# CPU_STM32F4.net
KiCad netlist of a schematic drawn in Altium Designer
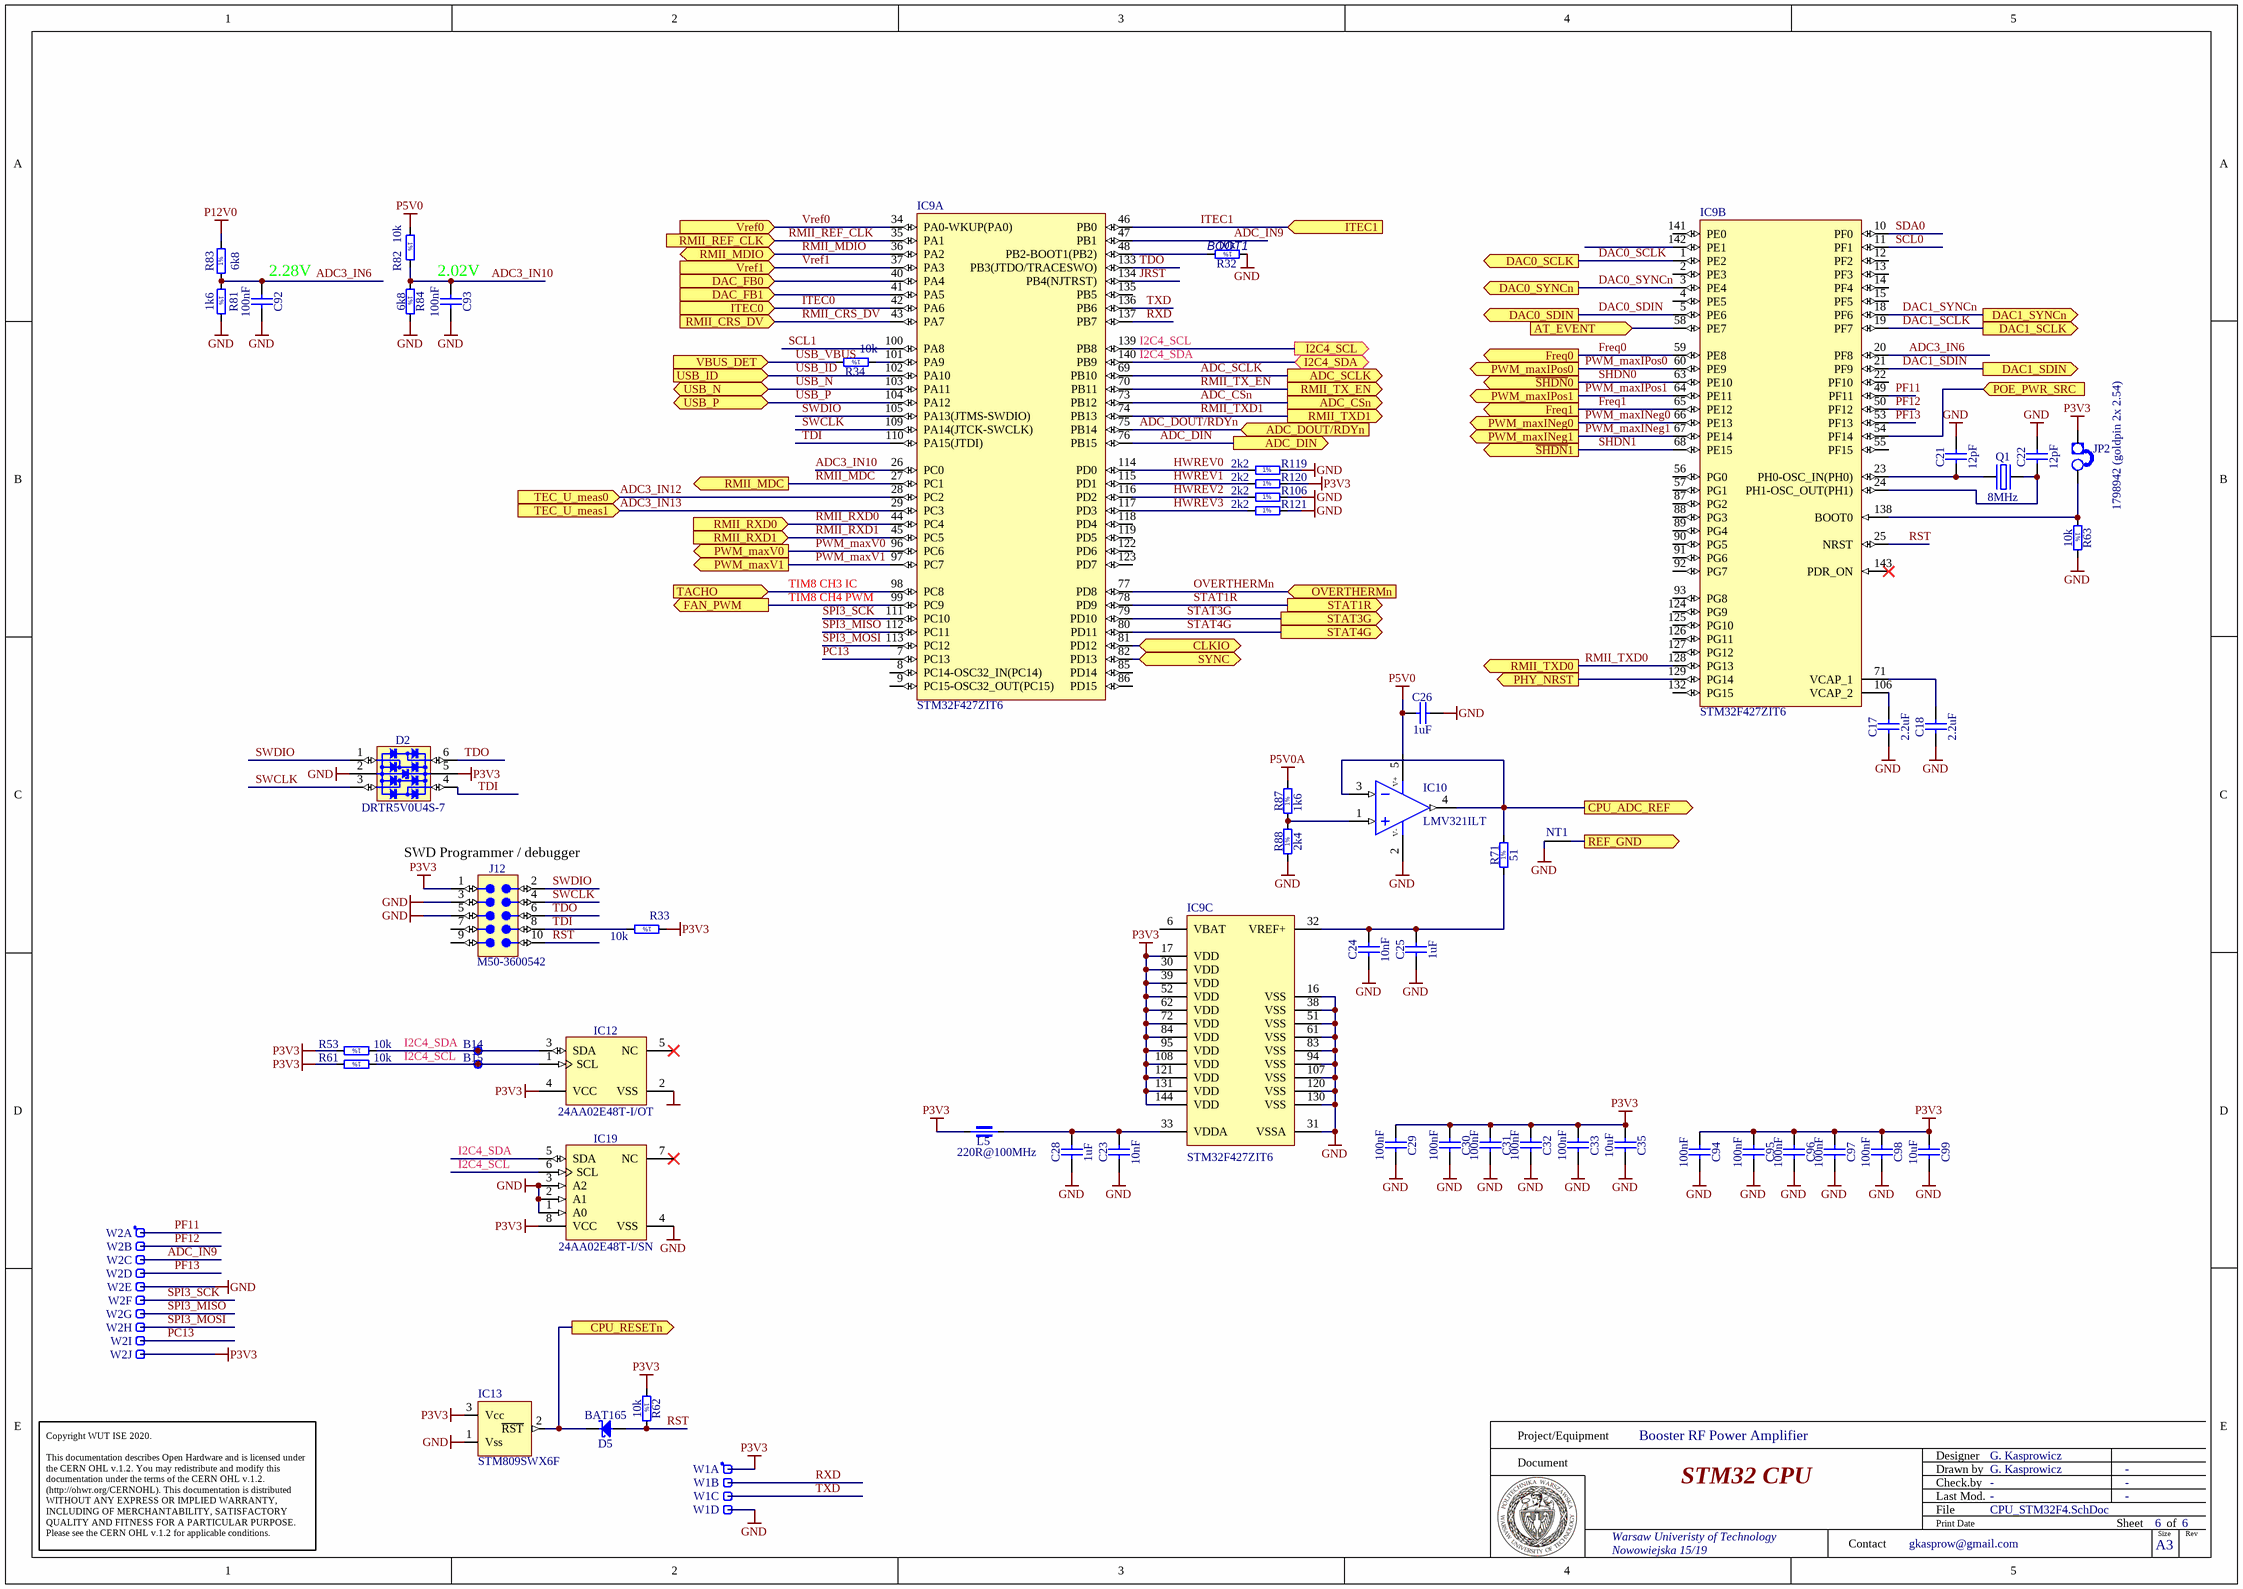
[diagram p0: CPU_STM32F4.SchDoc]

(export (version "E")
  (design (tool "Eeschema 10.0.6"))
  (components
    (comp (ref "B14")
      (value "SMD Pad")
      (footprint "C100")
      (description "Through Hole Pad")
      (fields (field (name "PART NUMBER") "SMD_PAD_D1MM") (field (name "AUTHOR") "CERN DEM JLC"))
      (libsource (lib "Eletro-mechanical") (part "Single SMD Pad (Round)"))
    )
    (comp (ref "B15")
      (value "SMD Pad")
      (footprint "C100")
      (description "Through Hole Pad")
      (fields (field (name "PART NUMBER") "SMD_PAD_D1MM") (field (name "AUTHOR") "CERN DEM JLC"))
      (libsource (lib "Eletro-mechanical") (part "Single SMD Pad (Round)"))
    )
    (comp (ref "C17")
      (value "2.2uF")
      (footprint "CAPC1608X90N")
      (description "Non-polarised capacitor")
      (fields
        (field (name "PART NUMBER") "CC0603_2.2UF_10V_20%_X7R")
        (field (name "VOLTAGE") "10V")
        (field (name "AUTHOR") "CERN DEM JLC")
      )
      (libsource (lib "Capacitors") (part "Capacitor - non polarized"))
    )
    (comp (ref "C18")
      (value "2.2uF")
      (footprint "CAPC1608X90N")
      (description "Non-polarised capacitor")
      (fields
        (field (name "PART NUMBER") "CC0603_2.2UF_10V_20%_X7R")
        (field (name "VOLTAGE") "10V")
        (field (name "AUTHOR") "CERN DEM JLC")
      )
      (libsource (lib "Capacitors") (part "Capacitor - non polarized"))
    )
    (comp (ref "C21")
      (value "12pF")
      (footprint "CAPC1005X55N")
      (description "Non-polarised capacitor")
      (fields
        (field (name "PART NUMBER") "CC0402_12PF_50V_5%_C0G")
        (field (name "VOLTAGE") "50V")
        (field (name "AUTHOR") "CERN DEM JLC")
      )
      (libsource (lib "Capacitors") (part "Capacitor - non polarized"))
    )
    (comp (ref "C22")
      (value "12pF")
      (footprint "CAPC1005X55N")
      (description "Non-polarised capacitor")
      (fields
        (field (name "PART NUMBER") "CC0402_12PF_50V_5%_C0G")
        (field (name "VOLTAGE") "50V")
        (field (name "AUTHOR") "CERN DEM JLC")
      )
      (libsource (lib "Capacitors") (part "Capacitor - non polarized"))
    )
    (comp (ref "C23")
      (value "10nF")
      (footprint "CAPC1005X55N")
      (description "Non-polarised capacitor")
      (fields
        (field (name "PART NUMBER") "CC0402_10NF_50V_10%_X7R")
        (field (name "VOLTAGE") "50V")
        (field (name "AUTHOR") "CERN DEM MR")
      )
      (libsource (lib "Capacitors") (part "Capacitor - non polarized"))
    )
    (comp (ref "C24")
      (value "10nF")
      (footprint "CAPC1005X55N")
      (description "Non-polarised capacitor")
      (fields
        (field (name "PART NUMBER") "CC0402_10NF_50V_10%_X7R")
        (field (name "VOLTAGE") "50V")
        (field (name "AUTHOR") "CERN DEM MR")
      )
      (libsource (lib "Capacitors") (part "Capacitor - non polarized"))
    )
    (comp (ref "C25")
      (value "1uF")
      (footprint "CAPC1608X87N")
      (description "Non-polarised capacitor")
      (fields
        (field (name "PART NUMBER") "CC0603_1UF_25V_10%_X7R")
        (field (name "VOLTAGE") "25V")
        (field (name "AUTHOR") "CERN DEM JLC")
      )
      (libsource (lib "Capacitors") (part "Capacitor - non polarized"))
    )
    (comp (ref "C26")
      (value "1uF")
      (footprint "CAPC1608X87N")
      (description "Non-polarised capacitor")
      (fields
        (field (name "PART NUMBER") "CC0603_1UF_25V_10%_X7R")
        (field (name "VOLTAGE") "25V")
        (field (name "AUTHOR") "CERN DEM JLC")
      )
      (libsource (lib "Capacitors") (part "Capacitor - non polarized"))
    )
    (comp (ref "C28")
      (value "1uF")
      (footprint "CAPC1608X87N")
      (description "Non-polarised capacitor")
      (fields
        (field (name "PART NUMBER") "CC0603_1UF_25V_10%_X7R")
        (field (name "VOLTAGE") "25V")
        (field (name "AUTHOR") "CERN DEM JLC")
      )
      (libsource (lib "Capacitors") (part "Capacitor - non polarized"))
    )
    (comp (ref "C29")
      (value "100nF")
      (footprint "CAPC1005X55N")
      (description "Non-polarised capacitor")
      (fields
        (field (name "PART NUMBER") "CC0402_100NF_16V_10%_X7R")
        (field (name "VOLTAGE") "16V")
        (field (name "AUTHOR") "CERN DEM JLC")
      )
      (libsource (lib "Capacitors") (part "Capacitor - non polarized"))
    )
    (comp (ref "C30")
      (value "100nF")
      (footprint "CAPC1005X55N")
      (description "Non-polarised capacitor")
      (fields
        (field (name "PART NUMBER") "CC0402_100NF_16V_10%_X7R")
        (field (name "VOLTAGE") "16V")
        (field (name "AUTHOR") "CERN DEM JLC")
      )
      (libsource (lib "Capacitors") (part "Capacitor - non polarized"))
    )
    (comp (ref "C31")
      (value "100nF")
      (footprint "CAPC1005X55N")
      (description "Non-polarised capacitor")
      (fields
        (field (name "PART NUMBER") "CC0402_100NF_16V_10%_X7R")
        (field (name "VOLTAGE") "16V")
        (field (name "AUTHOR") "CERN DEM JLC")
      )
      (libsource (lib "Capacitors") (part "Capacitor - non polarized"))
    )
    (comp (ref "C32")
      (value "100nF")
      (footprint "CAPC1005X55N")
      (description "Non-polarised capacitor")
      (fields
        (field (name "PART NUMBER") "CC0402_100NF_16V_10%_X7R")
        (field (name "VOLTAGE") "16V")
        (field (name "AUTHOR") "CERN DEM JLC")
      )
      (libsource (lib "Capacitors") (part "Capacitor - non polarized"))
    )
    (comp (ref "C33")
      (value "100nF")
      (footprint "CAPC1005X55N")
      (description "Non-polarised capacitor")
      (fields
        (field (name "PART NUMBER") "CC0402_100NF_16V_10%_X7R")
        (field (name "VOLTAGE") "16V")
        (field (name "AUTHOR") "CERN DEM JLC")
      )
      (libsource (lib "Capacitors") (part "Capacitor - non polarized"))
    )
    (comp (ref "C35")
      (value "10uF")
      (footprint "CAPC2012X135N")
      (description "Non-polarised capacitor")
      (fields
        (field (name "PART NUMBER") "CC0805_10UF_16V_10%_X5R")
        (field (name "VOLTAGE") "16V")
        (field (name "AUTHOR") "CERN DEM JLC")
      )
      (libsource (lib "Capacitors") (part "Capacitor - non polarized"))
    )
    (comp (ref "C92")
      (value "100nF")
      (footprint "CAPC1005X55N")
      (description "Non-polarised capacitor")
      (fields
        (field (name "PART NUMBER") "CC0402_100NF_16V_10%_X5R")
        (field (name "VOLTAGE") "16V")
        (field (name "AUTHOR") "CERN DEM JLC")
      )
      (libsource (lib "Capacitors") (part "Capacitor - non polarized"))
    )
    (comp (ref "C93")
      (value "100nF")
      (footprint "CAPC1005X55N")
      (description "Non-polarised capacitor")
      (fields
        (field (name "PART NUMBER") "CC0402_100NF_16V_10%_X5R")
        (field (name "VOLTAGE") "16V")
        (field (name "AUTHOR") "CERN DEM JLC")
      )
      (libsource (lib "Capacitors") (part "Capacitor - non polarized"))
    )
    (comp (ref "C94")
      (value "100nF")
      (footprint "CAPC1005X55N")
      (description "Non-polarised capacitor")
      (fields
        (field (name "PART NUMBER") "CC0402_100NF_16V_10%_X7R")
        (field (name "VOLTAGE") "16V")
        (field (name "AUTHOR") "CERN DEM JLC")
      )
      (libsource (lib "Capacitors") (part "Capacitor - non polarized"))
    )
    (comp (ref "C95")
      (value "100nF")
      (footprint "CAPC1005X55N")
      (description "Non-polarised capacitor")
      (fields
        (field (name "PART NUMBER") "CC0402_100NF_16V_10%_X7R")
        (field (name "VOLTAGE") "16V")
        (field (name "AUTHOR") "CERN DEM JLC")
      )
      (libsource (lib "Capacitors") (part "Capacitor - non polarized"))
    )
    (comp (ref "C96")
      (value "100nF")
      (footprint "CAPC1005X55N")
      (description "Non-polarised capacitor")
      (fields
        (field (name "PART NUMBER") "CC0402_100NF_16V_10%_X7R")
        (field (name "VOLTAGE") "16V")
        (field (name "AUTHOR") "CERN DEM JLC")
      )
      (libsource (lib "Capacitors") (part "Capacitor - non polarized"))
    )
    (comp (ref "C97")
      (value "100nF")
      (footprint "CAPC1005X55N")
      (description "Non-polarised capacitor")
      (fields
        (field (name "PART NUMBER") "CC0402_100NF_16V_10%_X7R")
        (field (name "VOLTAGE") "16V")
        (field (name "AUTHOR") "CERN DEM JLC")
      )
      (libsource (lib "Capacitors") (part "Capacitor - non polarized"))
    )
    (comp (ref "C98")
      (value "100nF")
      (footprint "CAPC1005X55N")
      (description "Non-polarised capacitor")
      (fields
        (field (name "PART NUMBER") "CC0402_100NF_16V_10%_X7R")
        (field (name "VOLTAGE") "16V")
        (field (name "AUTHOR") "CERN DEM JLC")
      )
      (libsource (lib "Capacitors") (part "Capacitor - non polarized"))
    )
    (comp (ref "C99")
      (value "10uF")
      (footprint "CAPC2012X135N")
      (description "Non-polarised capacitor")
      (fields
        (field (name "PART NUMBER") "CC0805_10UF_16V_10%_X5R")
        (field (name "VOLTAGE") "16V")
        (field (name "AUTHOR") "CERN DEM JLC")
      )
      (libsource (lib "Capacitors") (part "Capacitor - non polarized"))
    )
    (comp (ref "D2")
      (value "DRTR5V0U4S-7")
      (footprint "SOT65P210X110-6N")
      (description "Integrated Quad Ultra-Low Capacitance ESD Protection")
      (fields (field (name "MANUFACTURER") "DIODES") (field (name "AUTHOR") "GK"))
      (libsource (lib "Diodes") (part "D_TVS_DRTR5V0U4S-7"))
    )
    (comp (ref "D5")
      (value "BAT165")
      (footprint "SOD2512X110N")
      (description "Schottky Diode")
      (fields
        (field (name "VOLTAGE") "40V")
        (field (name "POWER") "750mA")
        (field (name "AUTHOR") "CERN DEM JLC")
      )
      (libsource (lib "ICs And Semiconductors") (part "Diode Schottky"))
    )
    (comp (ref "IC9")
      (value "STM32F427ZIT6")
      (footprint "STM-LQFP144_V")
      (fields (field (name "MANUFACTURER") "STMicroelectronics"))
      (libsource (lib "Altium Content Vault") (part "MC-ARM-STM32F427-SQ144"))
    )
    (comp (ref "IC10")
      (value "LMV321ILT")
      (footprint "SOT95P280X145-5N")
      (description "Operational Amplifier")
      (fields (field (name "MANUFACTURER") "ST MICROELECTRONICS") (field (name "AUTHOR") "CERN DEM MR"))
      (libsource (lib "ICs And Semiconductors") (part "Operational Amplifier Type10"))
    )
    (comp (ref "IC12")
      (value "24AA02E48T-I/OT")
      (footprint "SOT95P280X145-5N")
      (description "1.7V-5.5V, 2K I2C Serial EEPROM With EUI-48 Node Identity")
      (fields (field (name "MANUFACTURER") "MICROCHIP TECHNOLOGY") (field (name "AUTHOR") "CERN DEM MR"))
      (libsource (lib "ICs And Semiconductors") (part "24AA02E48T-I/OT"))
    )
    (comp (ref "IC13")
      (value "STM809SWX6F")
      (footprint "SOT-23")
      (description "2.93V  Reset circuit")
      (libsource (lib "LIBRARY_SCH") (part "VMON_STM809"))
    )
    (comp (ref "IC19")
      (value "24AA02E48T-I/SN")
      (footprint "SOIC127P600X175-8N")
      (description "1.7V-5.5V, 2K I2C™ Serial EEPROMs with EUI-48™ Node Identity")
      (fields (field (name "MANUFACTURER") "MICROCHIP TECHNOLOGY") (field (name "AUTHOR") "GK"))
      (libsource (lib "ICS-logic") (part "MEM_24AA02E48T-I/SN"))
    )
    (comp (ref "J12")
      (value "Header 10")
      (footprint "HARWIN_M50-3600542")
      (description "10 Contacts - Pitch 1.27mm - Dual Row SMT Vertical Pin Header (Post Lead = 3mm, Insulator 1mm)")
      (fields
        (field (name "PART NUMBER") "HARWIN_M50-3600542")
        (field (name "MANUFACTURER") "HARWIN")
        (field (name "MANUFACTURER PART NUMBER") "M50-3600542")
        (field (name "AUTHOR") "GK")
      )
      (libsource (lib "Connectors") (part "CON_2x10 1.27 SMT_male_HARWIN"))
    )
    (comp (ref "JP2")
      (value "1798942 (goldpin 2x 2.54)")
      (footprint "jump")
      (description "Jumper")
      (libsource (lib "LIBRARY_SCH") (part "JUMPER"))
    )
    (comp (ref "L5")
      (value "220R@100MHz")
      (footprint "INDC1005X55N")
      (fields
        (field (name "PART NUMBER") "IND0402_MURATA_BLM15HB221SN1")
        (field (name "POWER") "250mA")
        (field (name "TOLERANCE") "±25%")
        (field (name "AUTHOR") "CERN DEM JLC")
      )
      (libsource (lib "Inductors & Transformers") (part "Ferrite Bead"))
    )
    (comp (ref "NT1")
      (value "Net Tie")
      (footprint "Net Tie")
      (fields (field (name "AUTHOR") "CERN DEM JLC"))
      (libsource (lib "Eletro-mechanical") (part "Net Tie"))
    )
    (comp (ref "Q1")
      (value "8MHz")
      (footprint "XTAL_TXC_7A")
      (description "Quartz Crystal")
      (fields
        (field (name "PART NUMBER") "XTAL_8MHZ_TXC_7A-8.000MAAE-T")
        (field (name "MANUFACTURER") "TXC CORPORATION")
        (field (name "AUTHOR") "CERN DEM JLC")
      )
      (libsource (lib "ICs And Semiconductors") (part "Quartz Crystal"))
    )
    (comp (ref "R32")
      (value "10k")
      (footprint "RESC1005X40N")
      (description "Resistor - 1%")
      (fields
        (field (name "PART NUMBER") "R0402_10K_1%_0.0625W_100PPM")
        (field (name "POWER") "0.0625W")
        (field (name "AUTHOR") "CERN DEM JLC")
      )
      (libsource (lib "Resistors") (part "Resistor - 1%"))
    )
    (comp (ref "R33")
      (value "10k")
      (footprint "RESC1005X40N")
      (description "Resistor - 1%")
      (fields
        (field (name "PART NUMBER") "R0402_10K_1%_0.0625W_100PPM")
        (field (name "POWER") "0.0625W")
        (field (name "AUTHOR") "CERN DEM JLC")
      )
      (libsource (lib "Resistors") (part "Resistor - 1%"))
    )
    (comp (ref "R34")
      (value "10k")
      (footprint "RESC1005X40N")
      (description "Resistor - 1%")
      (fields
        (field (name "PART NUMBER") "R0402_10K_1%_0.0625W_100PPM")
        (field (name "POWER") "0.0625W")
        (field (name "AUTHOR") "CERN DEM JLC")
      )
      (libsource (lib "Resistors") (part "Resistor - 1%"))
    )
    (comp (ref "R53")
      (value "10k")
      (footprint "RESC1005X40N")
      (description "Resistor - 1%")
      (fields
        (field (name "PART NUMBER") "R0402_10K_1%_0.0625W_100PPM")
        (field (name "POWER") "0.0625W")
        (field (name "AUTHOR") "CERN DEM JLC")
      )
      (libsource (lib "Resistors") (part "Resistor - 1%"))
    )
    (comp (ref "R61")
      (value "10k")
      (footprint "RESC1005X40N")
      (description "Resistor - 1%")
      (fields
        (field (name "PART NUMBER") "R0402_10K_1%_0.0625W_100PPM")
        (field (name "POWER") "0.0625W")
        (field (name "AUTHOR") "CERN DEM JLC")
      )
      (libsource (lib "Resistors") (part "Resistor - 1%"))
    )
    (comp (ref "R62")
      (value "10k")
      (footprint "RESC1005X40N")
      (description "Resistor - 1%")
      (fields
        (field (name "PART NUMBER") "R0402_10K_1%_0.0625W_100PPM")
        (field (name "POWER") "0.0625W")
        (field (name "AUTHOR") "CERN DEM JLC")
      )
      (libsource (lib "Resistors") (part "Resistor - 1%"))
    )
    (comp (ref "R63")
      (value "10k")
      (footprint "RESC1005X40N")
      (description "Resistor - 1%")
      (fields
        (field (name "PART NUMBER") "R0402_10K_1%_0.0625W_100PPM")
        (field (name "POWER") "0.0625W")
        (field (name "AUTHOR") "CERN DEM JLC")
      )
      (libsource (lib "Resistors") (part "Resistor - 1%"))
    )
    (comp (ref "R71")
      (value "51")
      (footprint "RESC1005X40N")
      (description "Resistor - 1%")
      (fields
        (field (name "PART NUMBER") "R0402_51R_1%_0.0625W_100PPM")
        (field (name "POWER") "0.0625W")
        (field (name "AUTHOR") "CERN DEM JLC")
      )
      (libsource (lib "Resistors") (part "Resistor - 1%"))
    )
    (comp (ref "R81")
      (value "1k6")
      (footprint "RESC1005X40N")
      (description "Resistor - 1%")
      (fields
        (field (name "PART NUMBER") "R0402_1K6_1%_0.0625W_100PPM")
        (field (name "POWER") "0.0625W")
        (field (name "AUTHOR") "CERN DEM JLC")
      )
      (libsource (lib "Resistors") (part "Resistor - 1%"))
    )
    (comp (ref "R82")
      (value "10k")
      (footprint "RESC1005X40N")
      (description "Resistor - 1%")
      (fields
        (field (name "PART NUMBER") "R0402_10K_1%_0.0625W_100PPM")
        (field (name "POWER") "0.0625W")
        (field (name "AUTHOR") "CERN DEM JLC")
      )
      (libsource (lib "Resistors") (part "Resistor - 1%"))
    )
    (comp (ref "R83")
      (value "6k8")
      (footprint "RESC1005X40N")
      (description "Resistor - 1%")
      (fields
        (field (name "PART NUMBER") "R0402_6K8_1%_0.0625W_100PPM")
        (field (name "POWER") "0.0625W")
        (field (name "AUTHOR") "CERN DEM JLC")
      )
      (libsource (lib "Resistors") (part "Resistor - 1%"))
    )
    (comp (ref "R84")
      (value "6k8")
      (footprint "RESC1005X40N")
      (description "Resistor - 1%")
      (fields
        (field (name "PART NUMBER") "R0402_6K8_1%_0.0625W_100PPM")
        (field (name "POWER") "0.0625W")
        (field (name "AUTHOR") "CERN DEM JLC")
      )
      (libsource (lib "Resistors") (part "Resistor - 1%"))
    )
    (comp (ref "R87")
      (value "1k6")
      (footprint "RESC1005X40N")
      (description "Resistor - 1%")
      (fields
        (field (name "PART NUMBER") "R0402_1K6_1%_0.0625W_100PPM")
        (field (name "POWER") "0.0625W")
        (field (name "AUTHOR") "CERN DEM JLC")
      )
      (libsource (lib "Resistors") (part "Resistor - 1%"))
    )
    (comp (ref "R88")
      (value "2k4")
      (footprint "RESC1005X40N")
      (description "Resistor - 1%")
      (fields
        (field (name "PART NUMBER") "R0402_2K4_1%_0.0625W_100PPM")
        (field (name "POWER") "0.0625W")
        (field (name "AUTHOR") "CERN DEM JLC")
      )
      (libsource (lib "Resistors") (part "Resistor - 1%"))
    )
    (comp (ref "R106")
      (value "2k2")
      (footprint "RESC1005X40N")
      (description "Resistor - 1%")
      (fields
        (field (name "PART NUMBER") "R0402_2K2_1%_0.0625W_100PPM")
        (field (name "POWER") "0.0625W")
        (field (name "AUTHOR") "CERN DEM JLC")
      )
      (libsource (lib "Resistors") (part "Resistor - 1%"))
    )
    (comp (ref "R119")
      (value "2k2")
      (footprint "RESC1005X40N")
      (description "Resistor - 1%")
      (fields
        (field (name "PART NUMBER") "R0402_2K2_1%_0.0625W_100PPM")
        (field (name "POWER") "0.0625W")
        (field (name "AUTHOR") "CERN DEM JLC")
      )
      (libsource (lib "Resistors") (part "Resistor - 1%"))
    )
    (comp (ref "R120")
      (value "2k2")
      (footprint "RESC1005X40N")
      (description "Resistor - 1%")
      (fields
        (field (name "PART NUMBER") "R0402_2K2_1%_0.0625W_100PPM")
        (field (name "POWER") "0.0625W")
        (field (name "AUTHOR") "CERN DEM JLC")
      )
      (libsource (lib "Resistors") (part "Resistor - 1%"))
    )
    (comp (ref "R121")
      (value "2k2")
      (footprint "RESC1005X40N")
      (description "Resistor - 1%")
      (fields
        (field (name "PART NUMBER") "R0402_2K2_1%_0.0625W_100PPM")
        (field (name "POWER") "0.0625W")
        (field (name "AUTHOR") "CERN DEM JLC")
      )
      (libsource (lib "Resistors") (part "Resistor - 1%"))
    )
    (comp (ref "W1")
      (value "Header 4")
      (footprint "SAMTEC_HTSW-104-23-L-S")
      (description "4 Mini Wire-Wrap Contact Strip Header")
      (fields
        (field (name "PART NUMBER") "SAMTEC_HTSW-104-23-L-S")
        (field (name "MANUFACTURER") "SAMTEC")
        (field (name "AUTHOR") "CERN DEM JLC")
      )
      (libsource (lib "Connectors") (part "Wire-Wrap Contact x4"))
    )
    (comp (ref "W2")
      (value "Header 10")
      (footprint "SAMTEC_MTLW-110-07-L-S-250")
      (description "10 Mini Wire-Wrap Contact Strip Header")
      (fields
        (field (name "PART NUMBER") "SAMTEC_MTLW-110-07-L-S-250")
        (field (name "MANUFACTURER") "SAMTEC")
        (field (name "AUTHOR") "CERN DEM JLC")
      )
      (libsource (lib "Connectors") (part "Wire-Wrap Contact x10"))
    )
  )
  (nets
    (net (code "1") (name "/ADC3_IN6") (class "Default")
      (node (ref "C92") (pin "1") (pinfunction "1_1") (pintype "passive"))
      (node (ref "IC9") (pin "20") (pinfunction "PF8_20") (pintype "bidirectional"))
      (node (ref "R81") (pin "1") (pinfunction "1_1") (pintype "passive"))
      (node (ref "R83") (pin "1") (pinfunction "1_1") (pintype "passive"))
    )
    (net (code "2") (name "/ADC3_IN10") (class "Default")
      (node (ref "C93") (pin "1") (pinfunction "1_1") (pintype "passive"))
      (node (ref "IC9") (pin "26") (pinfunction "PC0_26") (pintype "bidirectional"))
      (node (ref "R82") (pin "2") (pinfunction "2_2") (pintype "passive"))
      (node (ref "R84") (pin "1") (pinfunction "1_1") (pintype "passive"))
    )
    (net (code "3") (name "/ADC3_IN12") (class "Default")
      (node (ref "IC9") (pin "28") (pinfunction "PC2_28") (pintype "bidirectional"))
    )
    (net (code "4") (name "/ADC3_IN13") (class "Default")
      (node (ref "IC9") (pin "29") (pinfunction "PC3_29") (pintype "bidirectional"))
    )
    (net (code "5") (name "/ADC_CSn") (class "Default")
      (node (ref "IC9") (pin "73") (pinfunction "PB12_73") (pintype "bidirectional"))
    )
    (net (code "6") (name "/ADC_DIN") (class "Default")
      (node (ref "IC9") (pin "76") (pinfunction "PB15_76") (pintype "bidirectional"))
    )
    (net (code "7") (name "/ADC_DOUT{slash}RDYn") (class "Default")
      (node (ref "IC9") (pin "75") (pinfunction "PB14_75") (pintype "bidirectional"))
    )
    (net (code "8") (name "/ADC_IN9") (class "Default")
      (node (ref "IC9") (pin "47") (pinfunction "PB1_47") (pintype "bidirectional"))
      (node (ref "W2") (pin "3") (pinfunction "3_3") (pintype "bidirectional"))
    )
    (net (code "9") (name "/ADC_SCLK") (class "Default")
      (node (ref "IC9") (pin "69") (pinfunction "PB10_69") (pintype "bidirectional"))
    )
    (net (code "10") (name "/AT_EVENT") (class "Default")
      (node (ref "IC9") (pin "58") (pinfunction "PE7_58") (pintype "bidirectional"))
    )
    (net (code "11") (name "/CLKIO") (class "Default")
      (node (ref "IC9") (pin "81") (pinfunction "PD12_81") (pintype "bidirectional"))
    )
    (net (code "12") (name "/CPU_ADC_REF") (class "Default")
      (node (ref "IC10") (pin "3") (pinfunction "IN-_3") (pintype "input"))
      (node (ref "IC10") (pin "4") (pinfunction "OUT_4") (pintype "output"))
      (node (ref "R71") (pin "2") (pinfunction "2_2") (pintype "passive"))
    )
    (net (code "13") (name "/CPU_RESETn") (class "Default")
      (node (ref "D5") (pin "1") (pinfunction "C_1") (pintype "passive"))
      (node (ref "IC13") (pin "2") (pinfunction "~{RST}_2") (pintype "output"))
    )
    (net (code "14") (name "/DAC0_SCLK") (class "Default")
      (node (ref "IC9") (pin "1") (pinfunction "PE2_1") (pintype "bidirectional"))
    )
    (net (code "15") (name "/DAC0_SDIN") (class "Default")
      (node (ref "IC9") (pin "5") (pinfunction "PE6_5") (pintype "bidirectional"))
    )
    (net (code "16") (name "/DAC0_SYNCn") (class "Default")
      (node (ref "IC9") (pin "3") (pinfunction "PE4_3") (pintype "bidirectional"))
    )
    (net (code "17") (name "/DAC1_SCLK") (class "Default")
      (node (ref "IC9") (pin "19") (pinfunction "PF7_19") (pintype "bidirectional"))
    )
    (net (code "18") (name "/DAC1_SDIN") (class "Default")
      (node (ref "IC9") (pin "21") (pinfunction "PF9_21") (pintype "bidirectional"))
    )
    (net (code "19") (name "/DAC1_SYNCn") (class "Default")
      (node (ref "IC9") (pin "18") (pinfunction "PF6_18") (pintype "bidirectional"))
    )
    (net (code "20") (name "/DAC_FB0") (class "Default")
      (node (ref "IC9") (pin "40") (pinfunction "PA4_40") (pintype "bidirectional"))
    )
    (net (code "21") (name "/DAC_FB1") (class "Default")
      (node (ref "IC9") (pin "41") (pinfunction "PA5_41") (pintype "bidirectional"))
    )
    (net (code "22") (name "/FAN_PWM") (class "Default")
      (node (ref "IC9") (pin "99") (pinfunction "PC9_99") (pintype "bidirectional"))
    )
    (net (code "23") (name "/Freq0") (class "Default")
      (node (ref "IC9") (pin "59") (pinfunction "PE8_59") (pintype "bidirectional"))
    )
    (net (code "24") (name "/Freq1") (class "Default")
      (node (ref "IC9") (pin "65") (pinfunction "PE12_65") (pintype "bidirectional"))
    )
    (net (code "25") (name "/HWREV0") (class "Default")
      (node (ref "IC9") (pin "114") (pinfunction "PD0_114") (pintype "bidirectional"))
      (node (ref "R119") (pin "1") (pinfunction "1_1") (pintype "passive"))
    )
    (net (code "26") (name "/HWREV1") (class "Default")
      (node (ref "IC9") (pin "115") (pinfunction "PD1_115") (pintype "bidirectional"))
      (node (ref "R120") (pin "1") (pinfunction "1_1") (pintype "passive"))
    )
    (net (code "27") (name "/HWREV2") (class "Default")
      (node (ref "IC9") (pin "116") (pinfunction "PD2_116") (pintype "bidirectional"))
      (node (ref "R106") (pin "1") (pinfunction "1_1") (pintype "passive"))
    )
    (net (code "28") (name "/HWREV3") (class "Default")
      (node (ref "IC9") (pin "117") (pinfunction "PD3_117") (pintype "bidirectional"))
      (node (ref "R121") (pin "1") (pinfunction "1_1") (pintype "passive"))
    )
    (net (code "29") (name "/I2C4_SCL") (class "Default")
      (node (ref "B15") (pin "1") (pinfunction "1_1") (pintype "bidirectional"))
      (node (ref "IC12") (pin "1") (pinfunction "SCL_1") (pintype "input"))
      (node (ref "IC19") (pin "6") (pinfunction "SCL_6") (pintype "input"))
      (node (ref "IC9") (pin "139") (pinfunction "PB8_139") (pintype "bidirectional"))
      (node (ref "R61") (pin "1") (pinfunction "1_1") (pintype "passive"))
    )
    (net (code "30") (name "/I2C4_SDA") (class "Default")
      (node (ref "B14") (pin "1") (pinfunction "1_1") (pintype "bidirectional"))
      (node (ref "IC12") (pin "3") (pinfunction "SDA_3") (pintype "bidirectional"))
      (node (ref "IC19") (pin "5") (pinfunction "SDA_5") (pintype "bidirectional"))
      (node (ref "IC9") (pin "140") (pinfunction "PB9_140") (pintype "bidirectional"))
      (node (ref "R53") (pin "1") (pinfunction "1_1") (pintype "passive"))
    )
    (net (code "31") (name "/ITEC0") (class "Default")
      (node (ref "IC9") (pin "42") (pinfunction "PA6_42") (pintype "bidirectional"))
    )
    (net (code "32") (name "/ITEC1") (class "Default")
      (node (ref "IC9") (pin "46") (pinfunction "PB0_46") (pintype "bidirectional"))
    )
    (net (code "33") (name "/JRST") (class "Default")
      (node (ref "IC9") (pin "134") (pinfunction "PB4(NJTRST)_134") (pintype "bidirectional"))
    )
    (net (code "34") (name "/OVERTHERMn") (class "Default")
      (node (ref "IC9") (pin "77") (pinfunction "PD8_77") (pintype "bidirectional"))
    )
    (net (code "35") (name "/PC13") (class "Default")
      (node (ref "IC9") (pin "7") (pinfunction "PC13_7") (pintype "bidirectional"))
      (node (ref "W2") (pin "9") (pinfunction "9_9") (pintype "bidirectional"))
    )
    (net (code "36") (name "/PF11") (class "Default")
      (node (ref "IC9") (pin "49") (pinfunction "PF11_49") (pintype "bidirectional"))
      (node (ref "W2") (pin "1") (pinfunction "1_1") (pintype "bidirectional"))
    )
    (net (code "37") (name "/PF12") (class "Default")
      (node (ref "IC9") (pin "50") (pinfunction "PF12_50") (pintype "bidirectional"))
      (node (ref "W2") (pin "2") (pinfunction "2_2") (pintype "bidirectional"))
    )
    (net (code "38") (name "/PF13") (class "Default")
      (node (ref "IC9") (pin "53") (pinfunction "PF13_53") (pintype "bidirectional"))
      (node (ref "W2") (pin "4") (pinfunction "4_4") (pintype "bidirectional"))
    )
    (net (code "39") (name "/PHY_NRST") (class "Default")
      (node (ref "IC9") (pin "129") (pinfunction "PG14_129") (pintype "bidirectional"))
    )
    (net (code "40") (name "/POE_PWR_SRC") (class "Default")
      (node (ref "IC9") (pin "54") (pinfunction "PF14_54") (pintype "bidirectional"))
    )
    (net (code "41") (name "/PWM_maxINeg0") (class "Default")
      (node (ref "IC9") (pin "66") (pinfunction "PE13_66") (pintype "bidirectional"))
    )
    (net (code "42") (name "/PWM_maxINeg1") (class "Default")
      (node (ref "IC9") (pin "67") (pinfunction "PE14_67") (pintype "bidirectional"))
    )
    (net (code "43") (name "/PWM_maxIPos0") (class "Default")
      (node (ref "IC9") (pin "60") (pinfunction "PE9_60") (pintype "bidirectional"))
    )
    (net (code "44") (name "/PWM_maxIPos1") (class "Default")
      (node (ref "IC9") (pin "64") (pinfunction "PE11_64") (pintype "bidirectional"))
    )
    (net (code "45") (name "/PWM_maxV0") (class "Default")
      (node (ref "IC9") (pin "96") (pinfunction "PC6_96") (pintype "bidirectional"))
    )
    (net (code "46") (name "/PWM_maxV1") (class "Default")
      (node (ref "IC9") (pin "97") (pinfunction "PC7_97") (pintype "bidirectional"))
    )
    (net (code "47") (name "/REF_GND") (class "Default")
      (node (ref "NT1") (pin "2") (pinfunction "2_2") (pintype "bidirectional"))
    )
    (net (code "48") (name "/RMII_CRS_DV") (class "Default")
      (node (ref "IC9") (pin "43") (pinfunction "PA7_43") (pintype "bidirectional"))
    )
    (net (code "49") (name "/RMII_MDC") (class "Default")
      (node (ref "IC9") (pin "27") (pinfunction "PC1_27") (pintype "bidirectional"))
    )
    (net (code "50") (name "/RMII_MDIO") (class "Default")
      (node (ref "IC9") (pin "36") (pinfunction "PA2_36") (pintype "bidirectional"))
    )
    (net (code "51") (name "/RMII_REF_CLK") (class "Default")
      (node (ref "IC9") (pin "35") (pinfunction "PA1_35") (pintype "bidirectional"))
    )
    (net (code "52") (name "/RMII_RXD0") (class "Default")
      (node (ref "IC9") (pin "44") (pinfunction "PC4_44") (pintype "bidirectional"))
    )
    (net (code "53") (name "/RMII_RXD1") (class "Default")
      (node (ref "IC9") (pin "45") (pinfunction "PC5_45") (pintype "bidirectional"))
    )
    (net (code "54") (name "/RMII_TXD0") (class "Default")
      (node (ref "IC9") (pin "128") (pinfunction "PG13_128") (pintype "bidirectional"))
    )
    (net (code "55") (name "/RMII_TXD1") (class "Default")
      (node (ref "IC9") (pin "74") (pinfunction "PB13_74") (pintype "bidirectional"))
    )
    (net (code "56") (name "/RMII_TX_EN") (class "Default")
      (node (ref "IC9") (pin "70") (pinfunction "PB11_70") (pintype "bidirectional"))
    )
    (net (code "57") (name "/RST") (class "Default")
      (node (ref "D5") (pin "2") (pinfunction "A_2") (pintype "passive"))
      (node (ref "IC9") (pin "25") (pinfunction "NRST_25") (pintype "bidirectional"))
      (node (ref "J12") (pin "10") (pinfunction "10_10") (pintype "bidirectional"))
      (node (ref "R62") (pin "2") (pinfunction "2_2") (pintype "passive"))
    )
    (net (code "58") (name "/RXD") (class "Default")
      (node (ref "IC9") (pin "137") (pinfunction "PB7_137") (pintype "bidirectional"))
      (node (ref "W1") (pin "2") (pinfunction "2_2") (pintype "bidirectional"))
    )
    (net (code "59") (name "/SCL0") (class "Default")
      (node (ref "IC9") (pin "11") (pinfunction "PF1_11") (pintype "bidirectional"))
    )
    (net (code "60") (name "/SCL1") (class "Default")
      (node (ref "IC9") (pin "100") (pinfunction "PA8_100") (pintype "bidirectional"))
    )
    (net (code "61") (name "/SDA0") (class "Default")
      (node (ref "IC9") (pin "10") (pinfunction "PF0_10") (pintype "bidirectional"))
    )
    (net (code "62") (name "/SPI3_MISO") (class "Default")
      (node (ref "IC9") (pin "112") (pinfunction "PC11_112") (pintype "bidirectional"))
      (node (ref "W2") (pin "7") (pinfunction "7_7") (pintype "bidirectional"))
    )
    (net (code "63") (name "/SPI3_MOSI") (class "Default")
      (node (ref "IC9") (pin "113") (pinfunction "PC12_113") (pintype "bidirectional"))
      (node (ref "W2") (pin "8") (pinfunction "8_8") (pintype "bidirectional"))
    )
    (net (code "64") (name "/SPI3_SCK") (class "Default")
      (node (ref "IC9") (pin "111") (pinfunction "PC10_111") (pintype "bidirectional"))
      (node (ref "W2") (pin "6") (pinfunction "6_6") (pintype "bidirectional"))
    )
    (net (code "65") (name "/STAT1R") (class "Default")
      (node (ref "IC9") (pin "78") (pinfunction "PD9_78") (pintype "bidirectional"))
    )
    (net (code "66") (name "/STAT3G") (class "Default")
      (node (ref "IC9") (pin "79") (pinfunction "PD10_79") (pintype "bidirectional"))
    )
    (net (code "67") (name "/STAT4G") (class "Default")
      (node (ref "IC9") (pin "80") (pinfunction "PD11_80") (pintype "bidirectional"))
    )
    (net (code "68") (name "/SWCLK") (class "Default")
      (node (ref "D2") (pin "3") (pinfunction "I/O2_3") (pintype "bidirectional"))
      (node (ref "IC9") (pin "109") (pinfunction "PA14(JTCK-SWCLK)_109") (pintype "bidirectional"))
      (node (ref "J12") (pin "4") (pinfunction "4_4") (pintype "bidirectional"))
    )
    (net (code "69") (name "/SWDIO") (class "Default")
      (node (ref "D2") (pin "1") (pinfunction "I/O1_1") (pintype "bidirectional"))
      (node (ref "IC9") (pin "105") (pinfunction "PA13(JTMS-SWDIO)_105") (pintype "bidirectional"))
      (node (ref "J12") (pin "2") (pinfunction "2_2") (pintype "bidirectional"))
    )
    (net (code "70") (name "/SYNC") (class "Default")
      (node (ref "IC9") (pin "82") (pinfunction "PD13_82") (pintype "bidirectional"))
    )
    (net (code "71") (name "/TACHO") (class "Default")
      (node (ref "IC9") (pin "98") (pinfunction "PC8_98") (pintype "bidirectional"))
    )
    (net (code "72") (name "/TDI") (class "Default")
      (node (ref "D2") (pin "4") (pinfunction "I/O3_4") (pintype "bidirectional"))
      (node (ref "IC9") (pin "110") (pinfunction "PA15(JTDI)_110") (pintype "bidirectional"))
      (node (ref "J12") (pin "8") (pinfunction "8_8") (pintype "bidirectional"))
      (node (ref "R33") (pin "2") (pinfunction "2_2") (pintype "passive"))
    )
    (net (code "73") (name "/TDO") (class "Default")
      (node (ref "D2") (pin "6") (pinfunction "I/O4_6") (pintype "bidirectional"))
      (node (ref "IC9") (pin "133") (pinfunction "PB3(JTDO/TRACESWO)_133") (pintype "bidirectional"))
      (node (ref "J12") (pin "6") (pinfunction "6_6") (pintype "bidirectional"))
    )
    (net (code "74") (name "/TXD") (class "Default")
      (node (ref "IC9") (pin "136") (pinfunction "PB6_136") (pintype "bidirectional"))
      (node (ref "W1") (pin "3") (pinfunction "3_3") (pintype "bidirectional"))
    )
    (net (code "75") (name "/USB_ID") (class "Default")
      (node (ref "IC9") (pin "102") (pinfunction "PA10_102") (pintype "bidirectional"))
    )
    (net (code "76") (name "/USB_N") (class "Default")
      (node (ref "IC9") (pin "103") (pinfunction "PA11_103") (pintype "bidirectional"))
    )
    (net (code "77") (name "/USB_P") (class "Default")
      (node (ref "IC9") (pin "104") (pinfunction "PA12_104") (pintype "bidirectional"))
    )
    (net (code "78") (name "/USB_VBUS") (class "Default")
      (node (ref "R34") (pin "2") (pinfunction "2_2") (pintype "passive"))
    )
    (net (code "79") (name "/Vref0") (class "Default")
      (node (ref "IC9") (pin "34") (pinfunction "PA0-WKUP(PA0)_34") (pintype "bidirectional"))
    )
    (net (code "80") (name "/Vref1") (class "Default")
      (node (ref "IC9") (pin "37") (pinfunction "PA3_37") (pintype "bidirectional"))
    )
    (net (code "81") (name "/~{SHDN}0") (class "Default")
      (node (ref "IC9") (pin "63") (pinfunction "PE10_63") (pintype "bidirectional"))
    )
    (net (code "82") (name "/~{SHDN}1") (class "Default")
      (node (ref "IC9") (pin "68") (pinfunction "PE15_68") (pintype "bidirectional"))
    )
    (net (code "83") (name "GND") (class "Default")
      (node (ref "C17") (pin "1") (pinfunction "1_1") (pintype "passive"))
      (node (ref "C18") (pin "1") (pinfunction "1_1") (pintype "passive"))
      (node (ref "C21") (pin "2") (pinfunction "2_2") (pintype "passive"))
      (node (ref "C22") (pin "2") (pinfunction "2_2") (pintype "passive"))
      (node (ref "C23") (pin "1") (pinfunction "1_1") (pintype "passive"))
      (node (ref "C24") (pin "1") (pinfunction "1_1") (pintype "passive"))
      (node (ref "C25") (pin "1") (pinfunction "1_1") (pintype "passive"))
      (node (ref "C26") (pin "2") (pinfunction "2_2") (pintype "passive"))
      (node (ref "C28") (pin "1") (pinfunction "1_1") (pintype "passive"))
      (node (ref "C29") (pin "2") (pinfunction "2_2") (pintype "passive"))
      (node (ref "C30") (pin "2") (pinfunction "2_2") (pintype "passive"))
      (node (ref "C31") (pin "2") (pinfunction "2_2") (pintype "passive"))
      (node (ref "C32") (pin "2") (pinfunction "2_2") (pintype "passive"))
      (node (ref "C33") (pin "2") (pinfunction "2_2") (pintype "passive"))
      (node (ref "C35") (pin "2") (pinfunction "2_2") (pintype "passive"))
      (node (ref "C92") (pin "2") (pinfunction "2_2") (pintype "passive"))
      (node (ref "C93") (pin "2") (pinfunction "2_2") (pintype "passive"))
      (node (ref "C94") (pin "2") (pinfunction "2_2") (pintype "passive"))
      (node (ref "C95") (pin "2") (pinfunction "2_2") (pintype "passive"))
      (node (ref "C96") (pin "2") (pinfunction "2_2") (pintype "passive"))
      (node (ref "C97") (pin "2") (pinfunction "2_2") (pintype "passive"))
      (node (ref "C98") (pin "2") (pinfunction "2_2") (pintype "passive"))
      (node (ref "C99") (pin "2") (pinfunction "2_2") (pintype "passive"))
      (node (ref "D2") (pin "2") (pinfunction "GND_2") (pintype "power_in"))
      (node (ref "IC10") (pin "2") (pinfunction "V-_2") (pintype "power_in"))
      (node (ref "IC12") (pin "2") (pinfunction "VSS_2") (pintype "power_in"))
      (node (ref "IC13") (pin "1") (pinfunction "Vss_1") (pintype "power_in"))
      (node (ref "IC19") (pin "1") (pinfunction "A0_1") (pintype "input"))
      (node (ref "IC19") (pin "2") (pinfunction "A1_2") (pintype "input"))
      (node (ref "IC19") (pin "3") (pinfunction "A2_3") (pintype "input"))
      (node (ref "IC19") (pin "4") (pinfunction "VSS_4") (pintype "power_in"))
      (node (ref "IC9") (pin "107") (pinfunction "VSS_107") (pintype "power_in"))
      (node (ref "IC9") (pin "120") (pinfunction "VSS_120") (pintype "power_in"))
      (node (ref "IC9") (pin "130") (pinfunction "VSS_130") (pintype "power_in"))
      (node (ref "IC9") (pin "16") (pinfunction "VSS_16") (pintype "power_in"))
      (node (ref "IC9") (pin "31") (pinfunction "VSSA_31") (pintype "power_in"))
      (node (ref "IC9") (pin "38") (pinfunction "VSS_38") (pintype "power_in"))
      (node (ref "IC9") (pin "51") (pinfunction "VSS_51") (pintype "power_in"))
      (node (ref "IC9") (pin "61") (pinfunction "VSS_61") (pintype "power_in"))
      (node (ref "IC9") (pin "83") (pinfunction "VSS_83") (pintype "power_in"))
      (node (ref "IC9") (pin "94") (pinfunction "VSS_94") (pintype "power_in"))
      (node (ref "J12") (pin "3") (pinfunction "3_3") (pintype "bidirectional"))
      (node (ref "J12") (pin "5") (pinfunction "5_5") (pintype "bidirectional"))
      (node (ref "NT1") (pin "1") (pinfunction "1_1") (pintype "bidirectional"))
      (node (ref "R106") (pin "2") (pinfunction "2_2") (pintype "passive"))
      (node (ref "R119") (pin "2") (pinfunction "2_2") (pintype "passive"))
      (node (ref "R121") (pin "2") (pinfunction "2_2") (pintype "passive"))
      (node (ref "R32") (pin "1") (pinfunction "1_1") (pintype "passive"))
      (node (ref "R63") (pin "2") (pinfunction "2_2") (pintype "passive"))
      (node (ref "R81") (pin "2") (pinfunction "2_2") (pintype "passive"))
      (node (ref "R84") (pin "2") (pinfunction "2_2") (pintype "passive"))
      (node (ref "R88") (pin "1") (pinfunction "1_1") (pintype "passive"))
      (node (ref "W1") (pin "4") (pinfunction "4_4") (pintype "bidirectional"))
      (node (ref "W2") (pin "5") (pinfunction "5_5") (pintype "bidirectional"))
    )
    (net (code "84") (name "Net-(IC9A-PA9)") (class "Default")
      (node (ref "IC9") (pin "101") (pinfunction "PA9_101") (pintype "bidirectional"))
      (node (ref "R34") (pin "1") (pinfunction "1_1") (pintype "passive"))
    )
    (net (code "85") (name "Net-(IC9A-PB2-BOOT1(PB2))") (class "Default")
      (node (ref "IC9") (pin "48") (pinfunction "PB2-BOOT1(PB2)_48") (pintype "bidirectional"))
      (node (ref "R32") (pin "2") (pinfunction "2_2") (pintype "passive"))
    )
    (net (code "86") (name "Net-(IC9B-BOOT0)") (class "Default")
      (node (ref "IC9") (pin "138") (pinfunction "BOOT0_138") (pintype "input"))
      (node (ref "JP2") (pin "2") (pinfunction "E2_2") (pintype "passive"))
      (node (ref "R63") (pin "1") (pinfunction "1_1") (pintype "passive"))
    )
    (net (code "87") (name "Net-(IC9B-PH0-OSC_IN(PH0))") (class "Default")
      (node (ref "C21") (pin "1") (pinfunction "1_1") (pintype "passive"))
      (node (ref "IC9") (pin "23") (pinfunction "PH0-OSC_IN(PH0)_23") (pintype "bidirectional"))
      (node (ref "Q1") (pin "1") (pinfunction "OSC1_1") (pintype "passive"))
    )
    (net (code "88") (name "Net-(IC9B-PH1-OSC_OUT(PH1))") (class "Default")
      (node (ref "C22") (pin "1") (pinfunction "1_1") (pintype "passive"))
      (node (ref "IC9") (pin "24") (pinfunction "PH1-OSC_OUT(PH1)_24") (pintype "bidirectional"))
      (node (ref "Q1") (pin "2") (pinfunction "OSC2_2") (pintype "passive"))
    )
    (net (code "89") (name "Net-(IC9B-VCAP_1)") (class "Default")
      (node (ref "C18") (pin "2") (pinfunction "2_2") (pintype "passive"))
      (node (ref "IC9") (pin "71") (pinfunction "VCAP_1_71") (pintype "power_in"))
    )
    (net (code "90") (name "Net-(IC9B-VCAP_2)") (class "Default")
      (node (ref "C17") (pin "2") (pinfunction "2_2") (pintype "passive"))
      (node (ref "IC9") (pin "106") (pinfunction "VCAP_2_106") (pintype "power_in"))
    )
    (net (code "91") (name "Net-(IC9C-VDDA)") (class "Default")
      (node (ref "C23") (pin "2") (pinfunction "2_2") (pintype "passive"))
      (node (ref "C28") (pin "2") (pinfunction "2_2") (pintype "passive"))
      (node (ref "IC9") (pin "33") (pinfunction "VDDA_33") (pintype "power_in"))
      (node (ref "L5") (pin "1") (pinfunction "1_1") (pintype "passive"))
    )
    (net (code "92") (name "Net-(IC9C-VREF+)") (class "Default")
      (node (ref "C24") (pin "2") (pinfunction "2_2") (pintype "passive"))
      (node (ref "C25") (pin "2") (pinfunction "2_2") (pintype "passive"))
      (node (ref "IC9") (pin "32") (pinfunction "VREF+_32") (pintype "power_in"))
      (node (ref "R71") (pin "1") (pinfunction "1_1") (pintype "passive"))
    )
    (net (code "93") (name "Net-(IC10-IN+)") (class "Default")
      (node (ref "IC10") (pin "1") (pinfunction "IN+_1") (pintype "input"))
      (node (ref "R87") (pin "1") (pinfunction "1_1") (pintype "passive"))
      (node (ref "R88") (pin "2") (pinfunction "2_2") (pintype "passive"))
    )
    (net (code "94") (name "P3V3") (class "Default")
      (node (ref "C29") (pin "1") (pinfunction "1_1") (pintype "passive"))
      (node (ref "C30") (pin "1") (pinfunction "1_1") (pintype "passive"))
      (node (ref "C31") (pin "1") (pinfunction "1_1") (pintype "passive"))
      (node (ref "C32") (pin "1") (pinfunction "1_1") (pintype "passive"))
      (node (ref "C33") (pin "1") (pinfunction "1_1") (pintype "passive"))
      (node (ref "C35") (pin "1") (pinfunction "1_1") (pintype "passive"))
      (node (ref "C94") (pin "1") (pinfunction "1_1") (pintype "passive"))
      (node (ref "C95") (pin "1") (pinfunction "1_1") (pintype "passive"))
      (node (ref "C96") (pin "1") (pinfunction "1_1") (pintype "passive"))
      (node (ref "C97") (pin "1") (pinfunction "1_1") (pintype "passive"))
      (node (ref "C98") (pin "1") (pinfunction "1_1") (pintype "passive"))
      (node (ref "C99") (pin "1") (pinfunction "1_1") (pintype "passive"))
      (node (ref "D2") (pin "5") (pinfunction "VBUS_5") (pintype "power_in"))
      (node (ref "IC12") (pin "4") (pinfunction "VCC_4") (pintype "power_in"))
      (node (ref "IC13") (pin "3") (pinfunction "Vcc_3") (pintype "power_in"))
      (node (ref "IC19") (pin "8") (pinfunction "VCC_8") (pintype "power_in"))
      (node (ref "IC9") (pin "108") (pinfunction "VDD_108") (pintype "power_in"))
      (node (ref "IC9") (pin "121") (pinfunction "VDD_121") (pintype "power_in"))
      (node (ref "IC9") (pin "131") (pinfunction "VDD_131") (pintype "power_in"))
      (node (ref "IC9") (pin "144") (pinfunction "VDD_144") (pintype "power_in"))
      (node (ref "IC9") (pin "17") (pinfunction "VDD_17") (pintype "power_in"))
      (node (ref "IC9") (pin "30") (pinfunction "VDD_30") (pintype "power_in"))
      (node (ref "IC9") (pin "39") (pinfunction "VDD_39") (pintype "power_in"))
      (node (ref "IC9") (pin "52") (pinfunction "VDD_52") (pintype "power_in"))
      (node (ref "IC9") (pin "62") (pinfunction "VDD_62") (pintype "power_in"))
      (node (ref "IC9") (pin "72") (pinfunction "VDD_72") (pintype "power_in"))
      (node (ref "IC9") (pin "84") (pinfunction "VDD_84") (pintype "power_in"))
      (node (ref "IC9") (pin "95") (pinfunction "VDD_95") (pintype "power_in"))
      (node (ref "J12") (pin "1") (pinfunction "1_1") (pintype "bidirectional"))
      (node (ref "JP2") (pin "1") (pinfunction "E1_1") (pintype "passive"))
      (node (ref "L5") (pin "2") (pinfunction "2_2") (pintype "passive"))
      (node (ref "R120") (pin "2") (pinfunction "2_2") (pintype "passive"))
      (node (ref "R33") (pin "1") (pinfunction "1_1") (pintype "passive"))
      (node (ref "R53") (pin "2") (pinfunction "2_2") (pintype "passive"))
      (node (ref "R61") (pin "2") (pinfunction "2_2") (pintype "passive"))
      (node (ref "R62") (pin "1") (pinfunction "1_1") (pintype "passive"))
      (node (ref "W1") (pin "1") (pinfunction "1_1") (pintype "bidirectional"))
      (node (ref "W2") (pin "10") (pinfunction "10_10") (pintype "bidirectional"))
    )
    (net (code "95") (name "P5V0") (class "Default")
      (node (ref "C26") (pin "1") (pinfunction "1_1") (pintype "passive"))
      (node (ref "IC10") (pin "5") (pinfunction "V+_5") (pintype "power_in"))
      (node (ref "R82") (pin "1") (pinfunction "1_1") (pintype "passive"))
    )
    (net (code "96") (name "P5V0A") (class "Default")
      (node (ref "R87") (pin "2") (pinfunction "2_2") (pintype "passive"))
    )
    (net (code "97") (name "P12V0") (class "Default")
      (node (ref "R83") (pin "2") (pinfunction "2_2") (pintype "passive"))
    )
    (net (code "98") (name "unconnected-(IC9A-PB5-Pad135)") (class "Default")
      (node (ref "IC9") (pin "135") (pinfunction "PB5_135") (pintype "bidirectional"))
    )
    (net (code "99") (name "unconnected-(IC9A-PC14-OSC32_IN(PC14)-Pad8)") (class "Default")
      (node (ref "IC9") (pin "8") (pinfunction "PC14-OSC32_IN(PC14)_8") (pintype "bidirectional"))
    )
    (net (code "100") (name "unconnected-(IC9A-PC15-OSC32_OUT(PC15)-Pad9)") (class "Default")
      (node (ref "IC9") (pin "9") (pinfunction "PC15-OSC32_OUT(PC15)_9") (pintype "bidirectional"))
    )
    (net (code "101") (name "unconnected-(IC9A-PD4-Pad118)") (class "Default")
      (node (ref "IC9") (pin "118") (pinfunction "PD4_118") (pintype "bidirectional"))
    )
    (net (code "102") (name "unconnected-(IC9A-PD5-Pad119)") (class "Default")
      (node (ref "IC9") (pin "119") (pinfunction "PD5_119") (pintype "bidirectional"))
    )
    (net (code "103") (name "unconnected-(IC9A-PD6-Pad122)") (class "Default")
      (node (ref "IC9") (pin "122") (pinfunction "PD6_122") (pintype "bidirectional"))
    )
    (net (code "104") (name "unconnected-(IC9A-PD7-Pad123)") (class "Default")
      (node (ref "IC9") (pin "123") (pinfunction "PD7_123") (pintype "bidirectional"))
    )
    (net (code "105") (name "unconnected-(IC9A-PD14-Pad85)") (class "Default")
      (node (ref "IC9") (pin "85") (pinfunction "PD14_85") (pintype "bidirectional"))
    )
    (net (code "106") (name "unconnected-(IC9A-PD15-Pad86)") (class "Default")
      (node (ref "IC9") (pin "86") (pinfunction "PD15_86") (pintype "bidirectional"))
    )
    (net (code "107") (name "unconnected-(IC9B-PDR_ON-Pad143)") (class "Default")
      (node (ref "IC9") (pin "143") (pinfunction "PDR_ON_143") (pintype "input+no_connect"))
    )
    (net (code "108") (name "unconnected-(IC9B-PE0-Pad141)") (class "Default")
      (node (ref "IC9") (pin "141") (pinfunction "PE0_141") (pintype "bidirectional"))
    )
    (net (code "109") (name "unconnected-(IC9B-PE1-Pad142)") (class "Default")
      (node (ref "IC9") (pin "142") (pinfunction "PE1_142") (pintype "bidirectional"))
    )
    (net (code "110") (name "unconnected-(IC9B-PE3-Pad2)") (class "Default")
      (node (ref "IC9") (pin "2") (pinfunction "PE3_2") (pintype "bidirectional"))
    )
    (net (code "111") (name "unconnected-(IC9B-PE5-Pad4)") (class "Default")
      (node (ref "IC9") (pin "4") (pinfunction "PE5_4") (pintype "bidirectional"))
    )
    (net (code "112") (name "unconnected-(IC9B-PF2-Pad12)") (class "Default")
      (node (ref "IC9") (pin "12") (pinfunction "PF2_12") (pintype "bidirectional"))
    )
    (net (code "113") (name "unconnected-(IC9B-PF3-Pad13)") (class "Default")
      (node (ref "IC9") (pin "13") (pinfunction "PF3_13") (pintype "bidirectional"))
    )
    (net (code "114") (name "unconnected-(IC9B-PF4-Pad14)") (class "Default")
      (node (ref "IC9") (pin "14") (pinfunction "PF4_14") (pintype "bidirectional"))
    )
    (net (code "115") (name "unconnected-(IC9B-PF5-Pad15)") (class "Default")
      (node (ref "IC9") (pin "15") (pinfunction "PF5_15") (pintype "bidirectional"))
    )
    (net (code "116") (name "unconnected-(IC9B-PF10-Pad22)") (class "Default")
      (node (ref "IC9") (pin "22") (pinfunction "PF10_22") (pintype "bidirectional"))
    )
    (net (code "117") (name "unconnected-(IC9B-PF15-Pad55)") (class "Default")
      (node (ref "IC9") (pin "55") (pinfunction "PF15_55") (pintype "bidirectional"))
    )
    (net (code "118") (name "unconnected-(IC9B-PG0-Pad56)") (class "Default")
      (node (ref "IC9") (pin "56") (pinfunction "PG0_56") (pintype "bidirectional"))
    )
    (net (code "119") (name "unconnected-(IC9B-PG1-Pad57)") (class "Default")
      (node (ref "IC9") (pin "57") (pinfunction "PG1_57") (pintype "bidirectional"))
    )
    (net (code "120") (name "unconnected-(IC9B-PG2-Pad87)") (class "Default")
      (node (ref "IC9") (pin "87") (pinfunction "PG2_87") (pintype "bidirectional"))
    )
    (net (code "121") (name "unconnected-(IC9B-PG3-Pad88)") (class "Default")
      (node (ref "IC9") (pin "88") (pinfunction "PG3_88") (pintype "bidirectional"))
    )
    (net (code "122") (name "unconnected-(IC9B-PG4-Pad89)") (class "Default")
      (node (ref "IC9") (pin "89") (pinfunction "PG4_89") (pintype "bidirectional"))
    )
    (net (code "123") (name "unconnected-(IC9B-PG5-Pad90)") (class "Default")
      (node (ref "IC9") (pin "90") (pinfunction "PG5_90") (pintype "bidirectional"))
    )
    (net (code "124") (name "unconnected-(IC9B-PG6-Pad91)") (class "Default")
      (node (ref "IC9") (pin "91") (pinfunction "PG6_91") (pintype "bidirectional"))
    )
    (net (code "125") (name "unconnected-(IC9B-PG7-Pad92)") (class "Default")
      (node (ref "IC9") (pin "92") (pinfunction "PG7_92") (pintype "bidirectional"))
    )
    (net (code "126") (name "unconnected-(IC9B-PG8-Pad93)") (class "Default")
      (node (ref "IC9") (pin "93") (pinfunction "PG8_93") (pintype "bidirectional"))
    )
    (net (code "127") (name "unconnected-(IC9B-PG9-Pad124)") (class "Default")
      (node (ref "IC9") (pin "124") (pinfunction "PG9_124") (pintype "bidirectional"))
    )
    (net (code "128") (name "unconnected-(IC9B-PG10-Pad125)") (class "Default")
      (node (ref "IC9") (pin "125") (pinfunction "PG10_125") (pintype "bidirectional"))
    )
    (net (code "129") (name "unconnected-(IC9B-PG11-Pad126)") (class "Default")
      (node (ref "IC9") (pin "126") (pinfunction "PG11_126") (pintype "bidirectional"))
    )
    (net (code "130") (name "unconnected-(IC9B-PG12-Pad127)") (class "Default")
      (node (ref "IC9") (pin "127") (pinfunction "PG12_127") (pintype "bidirectional"))
    )
    (net (code "131") (name "unconnected-(IC9B-PG15-Pad132)") (class "Default")
      (node (ref "IC9") (pin "132") (pinfunction "PG15_132") (pintype "bidirectional"))
    )
    (net (code "132") (name "unconnected-(IC9C-VBAT-Pad6)") (class "Default")
      (node (ref "IC9") (pin "6") (pinfunction "VBAT_6") (pintype "power_in"))
    )
    (net (code "133") (name "unconnected-(IC12-NC-Pad5)") (class "Default")
      (node (ref "IC12") (pin "5") (pinfunction "NC_5") (pintype "passive+no_connect"))
    )
    (net (code "134") (name "unconnected-(IC19-NC-Pad7)") (class "Default")
      (node (ref "IC19") (pin "7") (pinfunction "NC_7") (pintype "passive+no_connect"))
    )
    (net (code "135") (name "unconnected-(J12-Pad7)") (class "Default")
      (node (ref "J12") (pin "7") (pinfunction "7_7") (pintype "bidirectional"))
    )
    (net (code "136") (name "unconnected-(J12-Pad9)") (class "Default")
      (node (ref "J12") (pin "9") (pinfunction "9_9") (pintype "bidirectional"))
    )
  )
)
